# STM32_AUX.net
KiCad netlist of a schematic drawn in Altium Designer
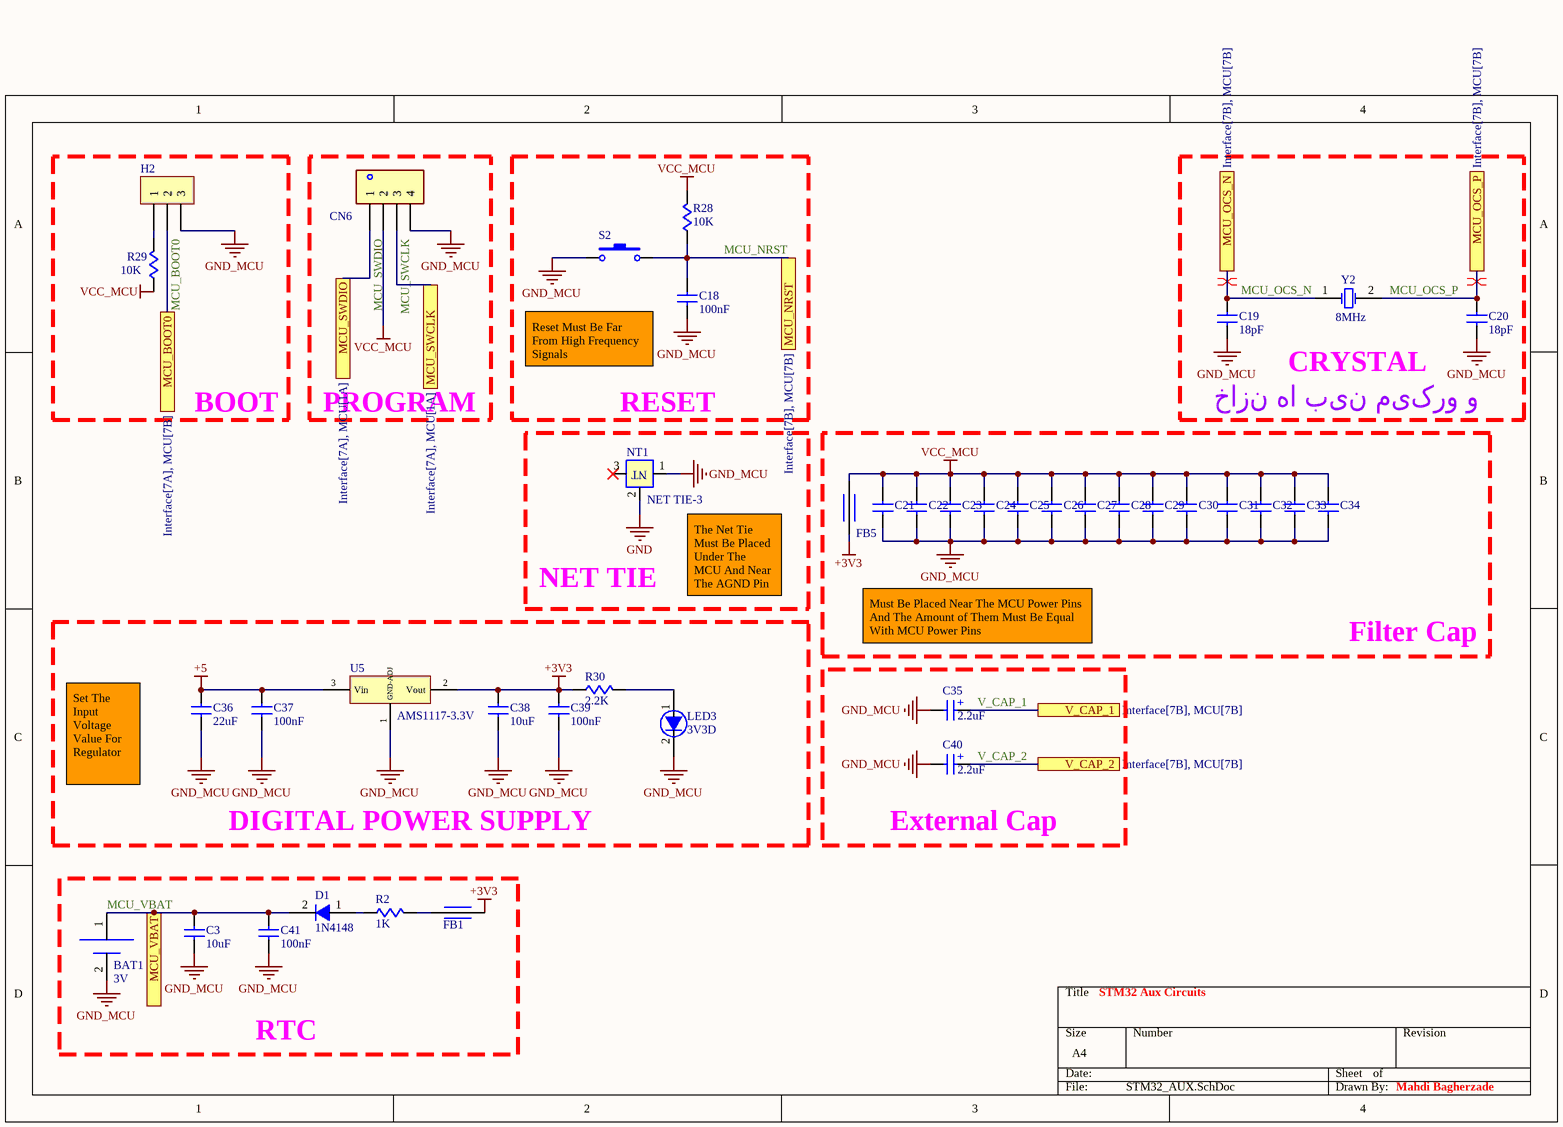
[diagram p0: STM32_AUX.SchDoc]

(export (version "E")
  (design (tool "Eeschema 10.0.6"))
  (components
    (comp (ref "BAT1")
      (value "Bat Holder 2016-SMD")
      (footprint "BAT-HOLDER-SMD-3V")
      (description "BATTERY")
      (fields (field (name "VOLTAGE") "3V") (field (name "PUBLISHER") "Mahdi Bagherzadeh"))
      (libsource (lib "Mahdi-Bagherzadeh") (part "BATTERY HOLDER"))
    )
    (comp (ref "C3")
      (value "10uF")
      (footprint "C-0805")
      (description "CAPACITOR")
      (fields
        (field (name "VOLTAGE") "50V")
        (field (name "TOLERANCE") "X7R")
        (field (name "PUBLISHER") "Mahdi Bagherzadeh")
      )
      (libsource (lib "Mahdi-Bagherzadeh") (part "CAP-CER"))
    )
    (comp (ref "C18")
      (value "100nF")
      (footprint "C-0805")
      (description "CAPACITOR")
      (fields
        (field (name "VOLTAGE") "50V")
        (field (name "TOLERANCE") "X7R")
        (field (name "PUBLISHER") "Mahdi Bagherzadeh")
      )
      (libsource (lib "Mahdi-Bagherzadeh") (part "CAP-CER"))
    )
    (comp (ref "C19")
      (value "18pF")
      (footprint "C-0805")
      (description "CAPACITOR")
      (fields
        (field (name "VOLTAGE") "50V")
        (field (name "TOLERANCE") "X7R")
        (field (name "PUBLISHER") "Mahdi Bagherzadeh")
      )
      (libsource (lib "Mahdi-Bagherzadeh") (part "CAP-CER"))
    )
    (comp (ref "C20")
      (value "18pF")
      (footprint "C-0805")
      (description "CAPACITOR")
      (fields
        (field (name "VOLTAGE") "50V")
        (field (name "TOLERANCE") "X7R")
        (field (name "PUBLISHER") "Mahdi Bagherzadeh")
      )
      (libsource (lib "Mahdi-Bagherzadeh") (part "CAP-CER"))
    )
    (comp (ref "C21")
      (value "CAP Cer 100nF-50V-X7R-SMD")
      (footprint "C-0805")
      (description "CAPACITOR")
      (fields
        (field (name "VOLTAGE") "50V")
        (field (name "TOLERANCE") "X7R")
        (field (name "PUBLISHER") "Mahdi Bagherzadeh")
      )
      (libsource (lib "Mahdi-Bagherzadeh") (part "CAP-CER"))
    )
    (comp (ref "C22")
      (value "CAP Cer 100nF-50V-X7R-SMD")
      (footprint "C-0805")
      (description "CAPACITOR")
      (fields
        (field (name "VOLTAGE") "50V")
        (field (name "TOLERANCE") "X7R")
        (field (name "PUBLISHER") "Mahdi Bagherzadeh")
      )
      (libsource (lib "Mahdi-Bagherzadeh") (part "CAP-CER"))
    )
    (comp (ref "C23")
      (value "CAP Cer 100nF-50V-X7R-SMD")
      (footprint "C-0805")
      (description "CAPACITOR")
      (fields
        (field (name "VOLTAGE") "50V")
        (field (name "TOLERANCE") "X7R")
        (field (name "PUBLISHER") "Mahdi Bagherzadeh")
      )
      (libsource (lib "Mahdi-Bagherzadeh") (part "CAP-CER"))
    )
    (comp (ref "C24")
      (value "CAP Cer 100nF-50V-X7R-SMD")
      (footprint "C-0805")
      (description "CAPACITOR")
      (fields
        (field (name "VOLTAGE") "50V")
        (field (name "TOLERANCE") "X7R")
        (field (name "PUBLISHER") "Mahdi Bagherzadeh")
      )
      (libsource (lib "Mahdi-Bagherzadeh") (part "CAP-CER"))
    )
    (comp (ref "C25")
      (value "CAP Cer 100nF-50V-X7R-SMD")
      (footprint "C-0805")
      (description "CAPACITOR")
      (fields
        (field (name "VOLTAGE") "50V")
        (field (name "TOLERANCE") "X7R")
        (field (name "PUBLISHER") "Mahdi Bagherzadeh")
      )
      (libsource (lib "Mahdi-Bagherzadeh") (part "CAP-CER"))
    )
    (comp (ref "C26")
      (value "CAP Cer 100nF-50V-X7R-SMD")
      (footprint "C-0805")
      (description "CAPACITOR")
      (fields
        (field (name "VOLTAGE") "50V")
        (field (name "TOLERANCE") "X7R")
        (field (name "PUBLISHER") "Mahdi Bagherzadeh")
      )
      (libsource (lib "Mahdi-Bagherzadeh") (part "CAP-CER"))
    )
    (comp (ref "C27")
      (value "CAP Cer 100nF-50V-X7R-SMD")
      (footprint "C-0805")
      (description "CAPACITOR")
      (fields
        (field (name "VOLTAGE") "50V")
        (field (name "TOLERANCE") "X7R")
        (field (name "PUBLISHER") "Mahdi Bagherzadeh")
      )
      (libsource (lib "Mahdi-Bagherzadeh") (part "CAP-CER"))
    )
    (comp (ref "C28")
      (value "CAP Cer 100nF-50V-X7R-SMD")
      (footprint "C-0805")
      (description "CAPACITOR")
      (fields
        (field (name "VOLTAGE") "50V")
        (field (name "TOLERANCE") "X7R")
        (field (name "PUBLISHER") "Mahdi Bagherzadeh")
      )
      (libsource (lib "Mahdi-Bagherzadeh") (part "CAP-CER"))
    )
    (comp (ref "C29")
      (value "CAP Cer 100nF-50V-X7R-SMD")
      (footprint "C-0805")
      (description "CAPACITOR")
      (fields
        (field (name "VOLTAGE") "50V")
        (field (name "TOLERANCE") "X7R")
        (field (name "PUBLISHER") "Mahdi Bagherzadeh")
      )
      (libsource (lib "Mahdi-Bagherzadeh") (part "CAP-CER"))
    )
    (comp (ref "C30")
      (value "CAP Cer 100nF-50V-X7R-SMD")
      (footprint "C-0805")
      (description "CAPACITOR")
      (fields
        (field (name "VOLTAGE") "50V")
        (field (name "TOLERANCE") "X7R")
        (field (name "PUBLISHER") "Mahdi Bagherzadeh")
      )
      (libsource (lib "Mahdi-Bagherzadeh") (part "CAP-CER"))
    )
    (comp (ref "C31")
      (value "CAP Cer 100nF-50V-X7R-SMD")
      (footprint "C-0805")
      (description "CAPACITOR")
      (fields
        (field (name "VOLTAGE") "50V")
        (field (name "TOLERANCE") "X7R")
        (field (name "PUBLISHER") "Mahdi Bagherzadeh")
      )
      (libsource (lib "Mahdi-Bagherzadeh") (part "CAP-CER"))
    )
    (comp (ref "C32")
      (value "CAP Cer 100nF-50V-X7R-SMD")
      (footprint "C-0805")
      (description "CAPACITOR")
      (fields
        (field (name "VOLTAGE") "50V")
        (field (name "TOLERANCE") "X7R")
        (field (name "PUBLISHER") "Mahdi Bagherzadeh")
      )
      (libsource (lib "Mahdi-Bagherzadeh") (part "CAP-CER"))
    )
    (comp (ref "C33")
      (value "CAP Cer 100nF-50V-X7R-SMD")
      (footprint "C-0805")
      (description "CAPACITOR")
      (fields
        (field (name "VOLTAGE") "50V")
        (field (name "TOLERANCE") "X7R")
        (field (name "PUBLISHER") "Mahdi Bagherzadeh")
      )
      (libsource (lib "Mahdi-Bagherzadeh") (part "CAP-CER"))
    )
    (comp (ref "C34")
      (value "CAP Cer 100nF-50V-X7R-SMD")
      (footprint "C-0805")
      (description "CAPACITOR")
      (fields
        (field (name "VOLTAGE") "50V")
        (field (name "TOLERANCE") "X7R")
        (field (name "PUBLISHER") "Mahdi Bagherzadeh")
      )
      (libsource (lib "Mahdi-Bagherzadeh") (part "CAP-CER"))
    )
    (comp (ref "C35")
      (value "2.2uF")
      (footprint "TAN-A")
      (description "CAPACITOR")
      (fields (field (name "VOLTAGE") "16V") (field (name "PUBLISHER") "Mahdi Bagherzadeh"))
      (libsource (lib "Mahdi-Bagherzadeh") (part "CAP-TAN"))
    )
    (comp (ref "C36")
      (value "22uF")
      (footprint "C-0805")
      (description "CAPACITOR")
      (fields
        (field (name "VOLTAGE") "50V")
        (field (name "TOLERANCE") "X7R")
        (field (name "PUBLISHER") "Mahdi Bagherzadeh")
      )
      (libsource (lib "Mahdi-Bagherzadeh") (part "CAP-CER"))
    )
    (comp (ref "C37")
      (value "100nF")
      (footprint "C-0805")
      (description "CAPACITOR")
      (fields
        (field (name "VOLTAGE") "50V")
        (field (name "TOLERANCE") "X7R")
        (field (name "PUBLISHER") "Mahdi Bagherzadeh")
      )
      (libsource (lib "Mahdi-Bagherzadeh") (part "CAP-CER"))
    )
    (comp (ref "C38")
      (value "10uF")
      (footprint "C-0805")
      (description "CAPACITOR")
      (fields
        (field (name "VOLTAGE") "50V")
        (field (name "TOLERANCE") "X7R")
        (field (name "PUBLISHER") "Mahdi Bagherzadeh")
      )
      (libsource (lib "Mahdi-Bagherzadeh") (part "CAP-CER"))
    )
    (comp (ref "C39")
      (value "100nF")
      (footprint "C-0805")
      (description "CAPACITOR")
      (fields
        (field (name "VOLTAGE") "50V")
        (field (name "TOLERANCE") "X7R")
        (field (name "PUBLISHER") "Mahdi Bagherzadeh")
      )
      (libsource (lib "Mahdi-Bagherzadeh") (part "CAP-CER"))
    )
    (comp (ref "C40")
      (value "2.2uF")
      (footprint "TAN-A")
      (description "CAPACITOR")
      (fields (field (name "VOLTAGE") "16V") (field (name "PUBLISHER") "Mahdi Bagherzadeh"))
      (libsource (lib "Mahdi-Bagherzadeh") (part "CAP-TAN"))
    )
    (comp (ref "C41")
      (value "100nF")
      (footprint "C-0805")
      (description "CAPACITOR")
      (fields
        (field (name "VOLTAGE") "50V")
        (field (name "TOLERANCE") "X7R")
        (field (name "PUBLISHER") "Mahdi Bagherzadeh")
      )
      (libsource (lib "Mahdi-Bagherzadeh") (part "CAP-CER"))
    )
    (comp (ref "CN6")
      (value "Connector XH/VH/TE-Straight/Right-THD/SMD-?mm")
      (footprint "XH-4")
      (description "CONNECTOR")
      (fields (field (name "PUBLISHER") "Mahdi Bagherzadeh"))
      (libsource (lib "Mahdi-Bagherzadeh") (part "CN-4pin"))
    )
    (comp (ref "D1")
      (value "Diode 1N4148-SMD")
      (footprint "SOD80")
      (description "DIODE")
      (fields (field (name "CODE") "1N4148") (field (name "PUBLISHER") "Mahdi Bagherzadeh"))
      (libsource (lib "Mahdi-Bagherzadeh") (part "DIODE"))
    )
    (comp (ref "FB1")
      (value "Ferrite Bead SMD")
      (footprint "FB-0805")
      (description "INDUCATOR")
      (fields (field (name "PUBLISHER") "Mahdi Bagherzadeh"))
      (libsource (lib "Mahdi-Bagherzadeh") (part "FERRITE BEAD"))
    )
    (comp (ref "FB5")
      (value "FERRITE BEAD")
      (footprint "FB-0805")
      (description "INDUCATOR")
      (fields (field (name "PUBLISHER") "Mahdi Bagherzadeh"))
      (libsource (lib "Mahdi-Bagherzadeh") (part "FERRITE BEAD"))
    )
    (comp (ref "H2")
      (value "BOOT")
      (footprint "H-3pin-M-S")
      (description "HEADER")
      (fields (field (name "PUBLISHER") "Mahdi Bagherzadeh"))
      (libsource (lib "Mahdi-Bagherzadeh") (part "HEADER-3pin"))
    )
    (comp (ref "LED3")
      (value "3V3D")
      (footprint "LED-1206-R")
      (description "LED")
      (fields (field (name "PUBLISHER") "Mahdi Bagherzadeh"))
      (libsource (lib "Mahdi-Bagherzadeh") (part "LED"))
    )
    (comp (ref "NT1")
      (value "NET TIE-3")
      (footprint "NET TIE-3")
      (fields (field (name "PUBLISHER") "Mahdi Bagherzadeh"))
      (libsource (lib "Mahdi-Bagherzadeh") (part "NET TIE-3"))
    )
    (comp (ref "R2")
      (value "1K")
      (footprint "R-0805")
      (description "RESISTOR")
      (fields
        (field (name "TOLERANCE") "5%")
        (field (name "POWER") "1/8W")
        (field (name "PUBLISHER") "Mahdi Bagherzadeh")
      )
      (libsource (lib "Mahdi-Bagherzadeh") (part "RES"))
    )
    (comp (ref "R28")
      (value "10K")
      (footprint "R-0805")
      (description "RESISTOR")
      (fields
        (field (name "POWER") "1/8W")
        (field (name "TOLERANCE") "5%")
        (field (name "PUBLISHER") "Mahdi Bagherzadeh")
      )
      (libsource (lib "Mahdi-Bagherzadeh") (part "RES"))
    )
    (comp (ref "R29")
      (value "10K")
      (footprint "R-0805")
      (description "RESISTOR")
      (fields
        (field (name "POWER") "1/8W")
        (field (name "TOLERANCE") "5%")
        (field (name "PUBLISHER") "Mahdi Bagherzadeh")
      )
      (libsource (lib "Mahdi-Bagherzadeh") (part "RES"))
    )
    (comp (ref "R30")
      (value "2.2K")
      (footprint "R-0805")
      (description "RESISTOR")
      (fields
        (field (name "POWER") "1/8W")
        (field (name "TOLERANCE") "5%")
        (field (name "PUBLISHER") "Mahdi Bagherzadeh")
      )
      (libsource (lib "Mahdi-Bagherzadeh") (part "RES"))
    )
    (comp (ref "S2")
      (value "RESET")
      (footprint "SW-SMD-2pin-3x6")
      (description "SWITCH")
      (fields (field (name "PUBLISHER") "Mahdi Bagherzadeh"))
      (libsource (lib "Mahdi-Bagherzadeh") (part "PUSH BUTTON"))
    )
    (comp (ref "U5")
      (value "AMS1117-3.3V")
      (footprint "SOT223")
      (description "REGULATOR")
      (fields (field (name "VOLTAGE") "?V") (field (name "PUBLISHER") "Mahdi Bagherzadeh"))
      (libsource (lib "Mahdi-Bagherzadeh") (part "AMS1117"))
    )
    (comp (ref "Y2")
      (value "8MHz")
      (footprint "CRYSTAL-SMD")
      (description "CRYSTAL")
      (fields (field (name "PUBLISHER") "Mahdi Bagherzadeh"))
      (libsource (lib "Mahdi-Bagherzadeh") (part "CRYSTAL"))
    )
  )
  (nets
    (net (code "1") (name "+3V3") (class "Default")
      (node (ref "C38") (pin "1") (pinfunction "1_1") (pintype "passive"))
      (node (ref "C39") (pin "1") (pinfunction "1_1") (pintype "passive"))
      (node (ref "FB1") (pin "1") (pinfunction "1_1") (pintype "passive"))
      (node (ref "FB5") (pin "1") (pinfunction "1_1") (pintype "passive"))
      (node (ref "R30") (pin "1") (pinfunction "1_1") (pintype "passive"))
      (node (ref "U5") (pin "2") (pinfunction "Vout_2") (pintype "power_in"))
    )
    (net (code "2") (name "+5") (class "Default")
      (node (ref "C36") (pin "1") (pinfunction "1_1") (pintype "passive"))
      (node (ref "C37") (pin "1") (pinfunction "1_1") (pintype "passive"))
      (node (ref "U5") (pin "3") (pinfunction "Vin_3") (pintype "power_in"))
    )
    (net (code "3") (name "/MCU_BOOT0") (class "Default")
      (node (ref "H2") (pin "2") (pinfunction "2_2") (pintype "passive"))
    )
    (net (code "4") (name "/MCU_NRST") (class "Default")
      (node (ref "C18") (pin "1") (pinfunction "1_1") (pintype "passive"))
      (node (ref "R28") (pin "1") (pinfunction "1_1") (pintype "passive"))
      (node (ref "S2") (pin "2") (pinfunction "2_2") (pintype "passive"))
    )
    (net (code "5") (name "/MCU_OCS_N") (class "Default")
      (node (ref "C19") (pin "1") (pinfunction "1_1") (pintype "passive"))
      (node (ref "Y2") (pin "1") (pinfunction "OSC1_1") (pintype "passive"))
    )
    (net (code "6") (name "/MCU_OCS_P") (class "Default")
      (node (ref "C20") (pin "1") (pinfunction "1_1") (pintype "passive"))
      (node (ref "Y2") (pin "2") (pinfunction "OSC2_2") (pintype "passive"))
    )
    (net (code "7") (name "/MCU_SWCLK") (class "Default")
      (node (ref "CN6") (pin "3") (pinfunction "3_3") (pintype "passive"))
    )
    (net (code "8") (name "/MCU_SWDIO") (class "Default")
      (node (ref "CN6") (pin "1") (pinfunction "1_1") (pintype "passive"))
    )
    (net (code "9") (name "/MCU_VBAT") (class "Default")
      (node (ref "BAT1") (pin "1") (pinfunction "+_1") (pintype "passive"))
      (node (ref "C3") (pin "2") (pinfunction "2_2") (pintype "passive"))
      (node (ref "C41") (pin "2") (pinfunction "2_2") (pintype "passive"))
      (node (ref "D1") (pin "2") (pinfunction "C_2") (pintype "passive"))
    )
    (net (code "10") (name "/V_CAP_1") (class "Default")
      (node (ref "C35") (pin "1") (pinfunction "1_1") (pintype "passive"))
    )
    (net (code "11") (name "/V_CAP_2") (class "Default")
      (node (ref "C40") (pin "1") (pinfunction "1_1") (pintype "passive"))
    )
    (net (code "12") (name "GND") (class "Default")
      (node (ref "NT1") (pin "2") (pinfunction "2_2") (pintype "passive"))
    )
    (net (code "13") (name "GND_MCU") (class "Default")
      (node (ref "BAT1") (pin "2") (pinfunction "-_2") (pintype "passive"))
      (node (ref "C18") (pin "2") (pinfunction "2_2") (pintype "passive"))
      (node (ref "C19") (pin "2") (pinfunction "2_2") (pintype "passive"))
      (node (ref "C20") (pin "2") (pinfunction "2_2") (pintype "passive"))
      (node (ref "C21") (pin "2") (pinfunction "2_2") (pintype "passive"))
      (node (ref "C22") (pin "2") (pinfunction "2_2") (pintype "passive"))
      (node (ref "C23") (pin "2") (pinfunction "2_2") (pintype "passive"))
      (node (ref "C24") (pin "2") (pinfunction "2_2") (pintype "passive"))
      (node (ref "C25") (pin "2") (pinfunction "2_2") (pintype "passive"))
      (node (ref "C26") (pin "2") (pinfunction "2_2") (pintype "passive"))
      (node (ref "C27") (pin "2") (pinfunction "2_2") (pintype "passive"))
      (node (ref "C28") (pin "2") (pinfunction "2_2") (pintype "passive"))
      (node (ref "C29") (pin "2") (pinfunction "2_2") (pintype "passive"))
      (node (ref "C3") (pin "1") (pinfunction "1_1") (pintype "passive"))
      (node (ref "C30") (pin "2") (pinfunction "2_2") (pintype "passive"))
      (node (ref "C31") (pin "2") (pinfunction "2_2") (pintype "passive"))
      (node (ref "C32") (pin "2") (pinfunction "2_2") (pintype "passive"))
      (node (ref "C33") (pin "2") (pinfunction "2_2") (pintype "passive"))
      (node (ref "C34") (pin "2") (pinfunction "2_2") (pintype "passive"))
      (node (ref "C35") (pin "2") (pinfunction "2_2") (pintype "passive"))
      (node (ref "C36") (pin "2") (pinfunction "2_2") (pintype "passive"))
      (node (ref "C37") (pin "2") (pinfunction "2_2") (pintype "passive"))
      (node (ref "C38") (pin "2") (pinfunction "2_2") (pintype "passive"))
      (node (ref "C39") (pin "2") (pinfunction "2_2") (pintype "passive"))
      (node (ref "C40") (pin "2") (pinfunction "2_2") (pintype "passive"))
      (node (ref "C41") (pin "1") (pinfunction "1_1") (pintype "passive"))
      (node (ref "CN6") (pin "4") (pinfunction "4_4") (pintype "passive"))
      (node (ref "H2") (pin "3") (pinfunction "3_3") (pintype "passive"))
      (node (ref "LED3") (pin "2") (pinfunction "C_2") (pintype "passive"))
      (node (ref "NT1") (pin "1") (pinfunction "1_1") (pintype "passive"))
      (node (ref "S2") (pin "1") (pinfunction "1_1") (pintype "passive"))
      (node (ref "U5") (pin "1") (pinfunction "GND-ADJ_1") (pintype "power_in"))
    )
    (net (code "14") (name "Net-(D1-A)") (class "Default")
      (node (ref "D1") (pin "1") (pinfunction "A_1") (pintype "passive"))
      (node (ref "R2") (pin "1") (pinfunction "1_1") (pintype "passive"))
    )
    (net (code "15") (name "Net-(FB1-Pad2)") (class "Default")
      (node (ref "FB1") (pin "2") (pinfunction "2_2") (pintype "passive"))
      (node (ref "R2") (pin "2") (pinfunction "2_2") (pintype "passive"))
    )
    (net (code "16") (name "Net-(H2-Pad1)") (class "Default")
      (node (ref "H2") (pin "1") (pinfunction "1_1") (pintype "passive"))
      (node (ref "R29") (pin "2") (pinfunction "2_2") (pintype "passive"))
    )
    (net (code "17") (name "Net-(LED3-A)") (class "Default")
      (node (ref "LED3") (pin "1") (pinfunction "A_1") (pintype "passive"))
      (node (ref "R30") (pin "2") (pinfunction "2_2") (pintype "passive"))
    )
    (net (code "18") (name "VCC_MCU") (class "Default")
      (node (ref "C21") (pin "1") (pinfunction "1_1") (pintype "passive"))
      (node (ref "C22") (pin "1") (pinfunction "1_1") (pintype "passive"))
      (node (ref "C23") (pin "1") (pinfunction "1_1") (pintype "passive"))
      (node (ref "C24") (pin "1") (pinfunction "1_1") (pintype "passive"))
      (node (ref "C25") (pin "1") (pinfunction "1_1") (pintype "passive"))
      (node (ref "C26") (pin "1") (pinfunction "1_1") (pintype "passive"))
      (node (ref "C27") (pin "1") (pinfunction "1_1") (pintype "passive"))
      (node (ref "C28") (pin "1") (pinfunction "1_1") (pintype "passive"))
      (node (ref "C29") (pin "1") (pinfunction "1_1") (pintype "passive"))
      (node (ref "C30") (pin "1") (pinfunction "1_1") (pintype "passive"))
      (node (ref "C31") (pin "1") (pinfunction "1_1") (pintype "passive"))
      (node (ref "C32") (pin "1") (pinfunction "1_1") (pintype "passive"))
      (node (ref "C33") (pin "1") (pinfunction "1_1") (pintype "passive"))
      (node (ref "C34") (pin "1") (pinfunction "1_1") (pintype "passive"))
      (node (ref "CN6") (pin "2") (pinfunction "2_2") (pintype "passive"))
      (node (ref "FB5") (pin "2") (pinfunction "2_2") (pintype "passive"))
      (node (ref "R28") (pin "2") (pinfunction "2_2") (pintype "passive"))
      (node (ref "R29") (pin "1") (pinfunction "1_1") (pintype "passive"))
    )
    (net (code "19") (name "unconnected-(NT1-Pad3)") (class "Default")
      (node (ref "NT1") (pin "3") (pinfunction "3_3") (pintype "passive+no_connect"))
    )
  )
)
